# LCD_Harness_B.net
KiCad netlist of a schematic drawn in EAGLE
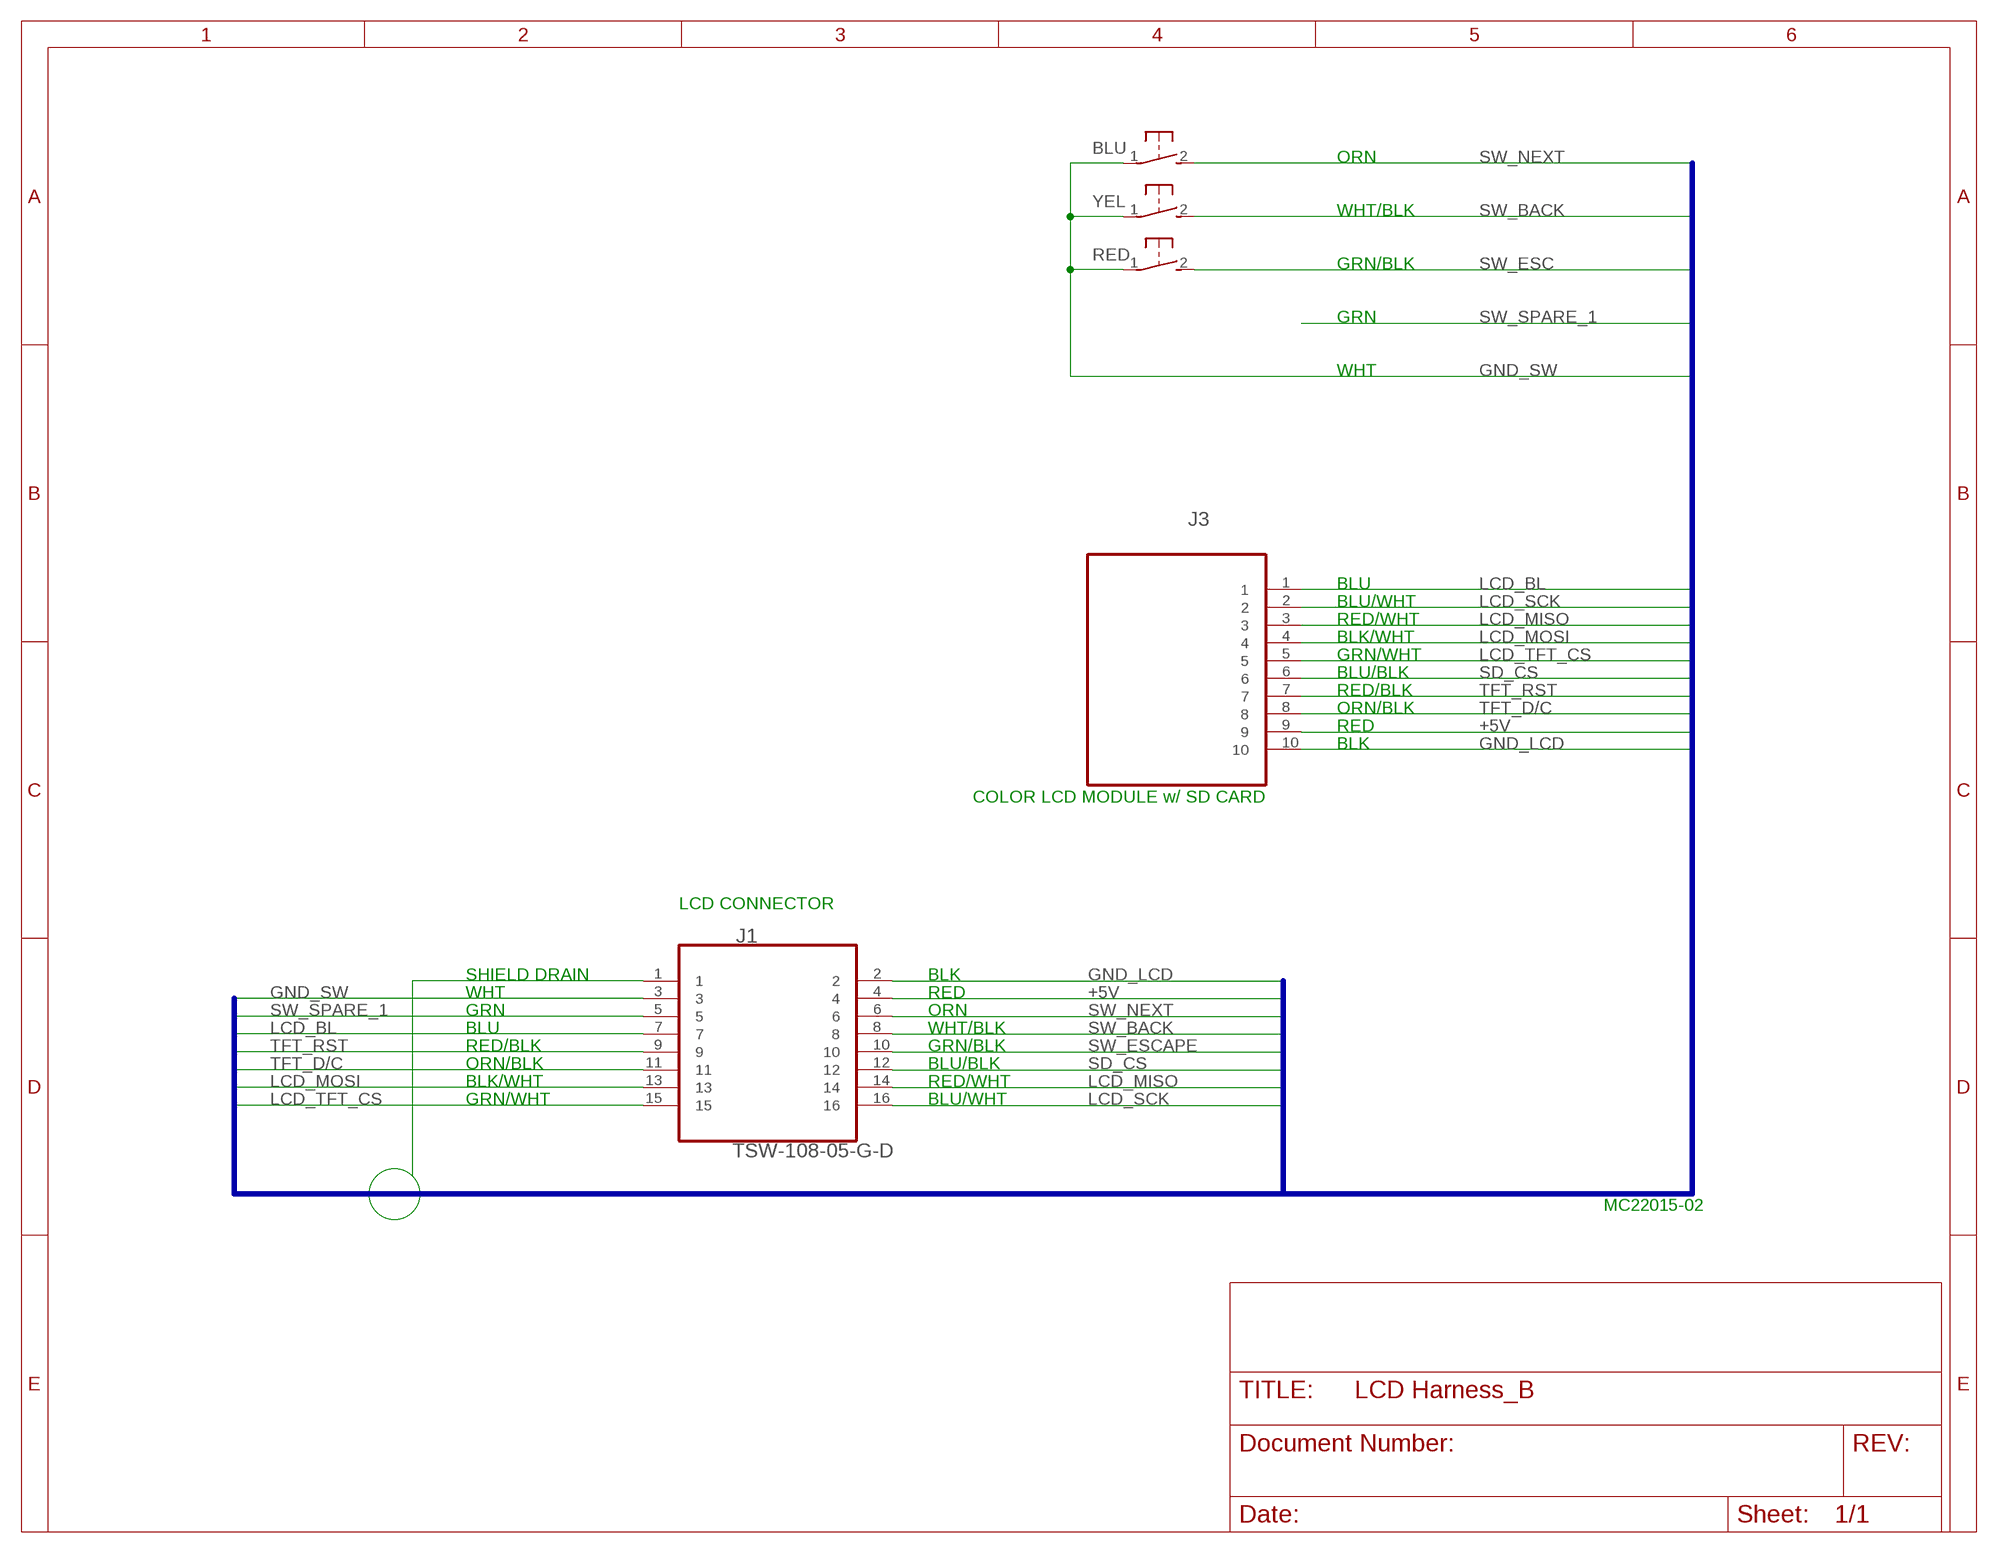
[diagram p0: schematic, sheet 1]

(export (version "E")
  (design (tool "Eeschema 10.0.6"))
  (components
    (comp (ref "BLU")
      (value "31-XX")
      (footprint "eagle-import:B3F-31XX")
      (fields (field (name "MPN") "B3F-3100"))
      (libsource (lib "eagle-import") (part "31-XX"))
    )
    (comp (ref "J1")
      (value "TSW-108-05-G-D")
      (footprint "eagle-import:SAMTEC_TSW-108-05-G-D")
      (libsource (lib "eagle-import") (part "TSW-108-05-G-D"))
    )
    (comp (ref "J3")
      (value "TSW-110-08-L-S-RA")
      (footprint "eagle-import:SAMTEC_TSW-110-08-L-S-RA")
      (libsource (lib "eagle-import") (part "TSW-110-08-L-S-RA"))
    )
    (comp (ref "RED")
      (value "31-XX")
      (footprint "eagle-import:B3F-31XX")
      (fields (field (name "MPN") "B3F-3100"))
      (libsource (lib "eagle-import") (part "31-XX"))
    )
    (comp (ref "YEL")
      (value "31-XX")
      (footprint "eagle-import:B3F-31XX")
      (fields (field (name "MPN") "B3F-3100"))
      (libsource (lib "eagle-import") (part "31-XX"))
    )
  )
  (nets
    (net (code "1") (name "/+5V") (class "Default")
      (node (ref "J1") (pin "4") (pinfunction "4_4") (pintype "passive"))
      (node (ref "J3") (pin "9") (pinfunction "9_9") (pintype "passive"))
    )
    (net (code "2") (name "/GND_LCD") (class "Default")
      (node (ref "J1") (pin "2") (pinfunction "2_2") (pintype "passive"))
      (node (ref "J3") (pin "10") (pinfunction "10_10") (pintype "passive"))
    )
    (net (code "3") (name "/GND_SW") (class "Default")
      (node (ref "BLU") (pin "1") (pinfunction "P_1") (pintype "passive"))
      (node (ref "J1") (pin "3") (pinfunction "3_3") (pintype "passive"))
      (node (ref "RED") (pin "1") (pinfunction "P_1") (pintype "passive"))
      (node (ref "YEL") (pin "1") (pinfunction "P_1") (pintype "passive"))
    )
    (net (code "4") (name "/LCD_BL") (class "Default")
      (node (ref "J1") (pin "7") (pinfunction "7_7") (pintype "passive"))
      (node (ref "J3") (pin "1") (pinfunction "1_1") (pintype "passive"))
    )
    (net (code "5") (name "/LCD_MISO") (class "Default")
      (node (ref "J1") (pin "14") (pinfunction "14_14") (pintype "passive"))
      (node (ref "J3") (pin "3") (pinfunction "3_3") (pintype "passive"))
    )
    (net (code "6") (name "/LCD_MOSI") (class "Default")
      (node (ref "J1") (pin "13") (pinfunction "13_13") (pintype "passive"))
      (node (ref "J3") (pin "4") (pinfunction "4_4") (pintype "passive"))
    )
    (net (code "7") (name "/LCD_SCK") (class "Default")
      (node (ref "J1") (pin "16") (pinfunction "16_16") (pintype "passive"))
      (node (ref "J3") (pin "2") (pinfunction "2_2") (pintype "passive"))
    )
    (net (code "8") (name "/LCD_TFT_CS") (class "Default")
      (node (ref "J1") (pin "15") (pinfunction "15_15") (pintype "passive"))
      (node (ref "J3") (pin "5") (pinfunction "5_5") (pintype "passive"))
    )
    (net (code "9") (name "/SD_CS") (class "Default")
      (node (ref "J1") (pin "12") (pinfunction "12_12") (pintype "passive"))
      (node (ref "J3") (pin "6") (pinfunction "6_6") (pintype "passive"))
    )
    (net (code "10") (name "/SW_BACK") (class "Default")
      (node (ref "J1") (pin "8") (pinfunction "8_8") (pintype "passive"))
      (node (ref "YEL") (pin "2") (pinfunction "S_2") (pintype "passive"))
    )
    (net (code "11") (name "/SW_ESC") (class "Default")
      (node (ref "RED") (pin "2") (pinfunction "S_2") (pintype "passive"))
    )
    (net (code "12") (name "/SW_ESCAPE") (class "Default")
      (node (ref "J1") (pin "10") (pinfunction "10_10") (pintype "passive"))
    )
    (net (code "13") (name "/SW_NEXT") (class "Default")
      (node (ref "BLU") (pin "2") (pinfunction "S_2") (pintype "passive"))
      (node (ref "J1") (pin "6") (pinfunction "6_6") (pintype "passive"))
    )
    (net (code "14") (name "/SW_SPARE_1") (class "Default")
      (node (ref "J1") (pin "5") (pinfunction "5_5") (pintype "passive"))
    )
    (net (code "15") (name "/TFT_D{slash}C") (class "Default")
      (node (ref "J1") (pin "11") (pinfunction "11_11") (pintype "passive"))
      (node (ref "J3") (pin "8") (pinfunction "8_8") (pintype "passive"))
    )
    (net (code "16") (name "/TFT_RST") (class "Default")
      (node (ref "J1") (pin "9") (pinfunction "9_9") (pintype "passive"))
      (node (ref "J3") (pin "7") (pinfunction "7_7") (pintype "passive"))
    )
    (net (code "17") (name "unconnected-(J1-Pad1)") (class "Default")
      (node (ref "J1") (pin "1") (pinfunction "1_1") (pintype "passive"))
    )
  )
)
